# Saules_kolektoriaus_valdiklis_v1_23.net
KiCad netlist of a schematic drawn in EAGLE
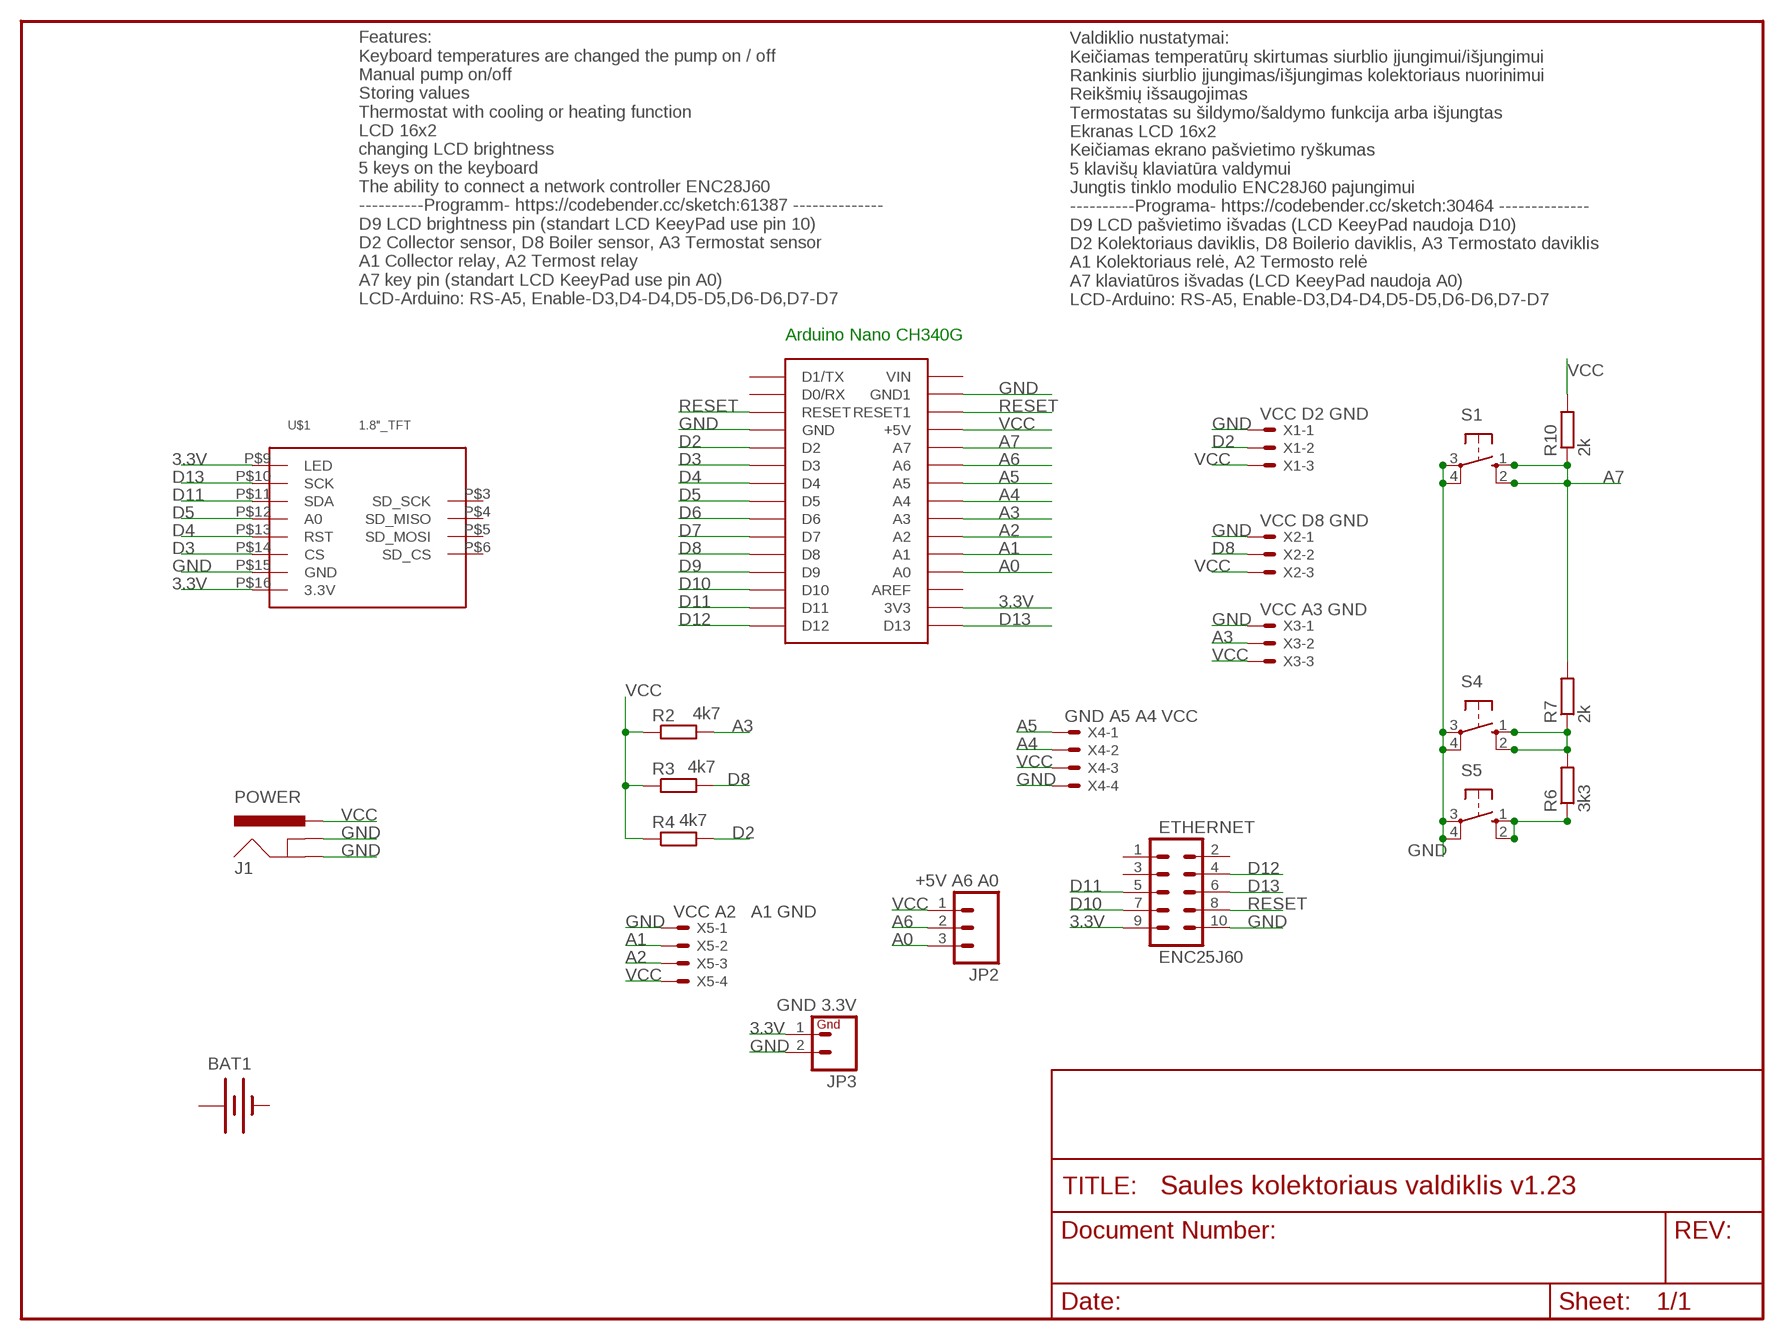
[diagram p0: schematic, sheet 1]

(export (version "E")
  (design (tool "Eeschema 10.0.6"))
  (components
    (comp (ref "ARDUINONANOCH340G")
      (value "ARDUINONANO")
      (footprint "eagle-import:PDIP-32")
      (libsource (lib "eagle-import") (part "ARDUINONANO"))
    )
    (comp (ref "BAT1")
      (value "BATTERY20PTH")
      (footprint "eagle-import:BATTCOM_20MM_PTH")
      (libsource (lib "eagle-import") (part "BATTERY20PTH"))
    )
    (comp (ref "ETHERNET")
      (value "ENC25J60")
      (footprint "eagle-import:AVR_ICSP")
      (libsource (lib "eagle-import") (part "M05X2PTH"))
    )
    (comp (ref "J1")
      (value "POWER")
      (footprint "eagle-import:POWER_JACK_PTH_LOCK")
      (libsource (lib "eagle-import") (part "POWER_JACKPTH_LOCK"))
    )
    (comp (ref "JP2")
      (value "+5V A6 A0")
      (footprint "eagle-import:1X03")
      (libsource (lib "eagle-import") (part "M03PTH"))
    )
    (comp (ref "JP3")
      (value "GND 3.3V")
      (footprint "eagle-import:1X02")
      (libsource (lib "eagle-import") (part "M02PTH"))
    )
    (comp (ref "R2")
      (value "4k7")
      (footprint "eagle-import:0207_10")
      (libsource (lib "eagle-import") (part "R-EU_0207/10"))
    )
    (comp (ref "R3")
      (value "4k7")
      (footprint "eagle-import:0207_10")
      (libsource (lib "eagle-import") (part "R-EU_0207/10"))
    )
    (comp (ref "R4")
      (value "4k7")
      (footprint "eagle-import:0207_10")
      (libsource (lib "eagle-import") (part "R-EU_0207/10"))
    )
    (comp (ref "R6")
      (value "3k3")
      (footprint "eagle-import:0207_10")
      (libsource (lib "eagle-import") (part "R-EU_0207/10"))
    )
    (comp (ref "R7")
      (value "2k")
      (footprint "eagle-import:0207_10")
      (libsource (lib "eagle-import") (part "R-EU_0207/10"))
    )
    (comp (ref "R10")
      (value "2k")
      (footprint "eagle-import:0207_10")
      (libsource (lib "eagle-import") (part "R-EU_0207/10"))
    )
    (comp (ref "S1")
      (value "10-XX")
      (footprint "eagle-import:B3F-10XX")
      (fields (field (name "MPN") "B3F-1000"))
      (libsource (lib "eagle-import") (part "10-XX"))
    )
    (comp (ref "S4")
      (value "10-XX")
      (footprint "eagle-import:B3F-10XX")
      (fields (field (name "MPN") "B3F-1000"))
      (libsource (lib "eagle-import") (part "10-XX"))
    )
    (comp (ref "S5")
      (value "10-XX")
      (footprint "eagle-import:B3F-10XX")
      (fields (field (name "MPN") "B3F-1000"))
      (libsource (lib "eagle-import") (part "10-XX"))
    )
    (comp (ref "U$1")
      (value "1.8\"_TFT")
      (footprint "eagle-import:1.8__TFT")
      (libsource (lib "eagle-import") (part "1.8{dblquote}_TFT"))
    )
    (comp (ref "X1")
      (value "VCC D2 GND")
      (footprint "eagle-import:22-23-2031")
      (fields (field (name "MF") "MOLEX") (field (name "MPN") "22-23-2031"))
      (libsource (lib "eagle-import") (part "22-23-2031"))
    )
    (comp (ref "X2")
      (value "VCC D8 GND")
      (footprint "eagle-import:22-23-2031")
      (fields (field (name "MF") "MOLEX") (field (name "MPN") "22-23-2031"))
      (libsource (lib "eagle-import") (part "22-23-2031"))
    )
    (comp (ref "X3")
      (value "VCC A3 GND")
      (footprint "eagle-import:22-23-2031")
      (fields (field (name "MF") "MOLEX") (field (name "MPN") "22-23-2031"))
      (libsource (lib "eagle-import") (part "22-23-2031"))
    )
    (comp (ref "X4")
      (value "GND A5 A4 VCC")
      (footprint "eagle-import:22-23-2041")
      (fields (field (name "MF") "MOLEX") (field (name "MPN") "22-23-2041"))
      (libsource (lib "eagle-import") (part "22-23-2041"))
    )
    (comp (ref "X5")
      (value "VCC A2 A1 GND")
      (footprint "eagle-import:22-23-2041")
      (fields (field (name "MF") "MOLEX") (field (name "MPN") "22-23-2041"))
      (libsource (lib "eagle-import") (part "22-23-2041"))
    )
  )
  (nets
    (net (code "1") (name "/+") (class "Default")
      (node (ref "BAT1") (pin "1") (pinfunction "+_1") (pintype "power_in"))
    )
    (net (code "2") (name "/-") (class "Default")
      (node (ref "BAT1") (pin "2") (pinfunction "-_2") (pintype "power_in"))
    )
    (net (code "3") (name "/3.3V") (class "Default")
      (node (ref "ARDUINONANOCH340G") (pin "3V3") (pinfunction "3V3_3V3") (pintype "bidirectional"))
      (node (ref "ETHERNET") (pin "9") (pinfunction "9_9") (pintype "passive"))
      (node (ref "JP3") (pin "1") (pinfunction "1_1") (pintype "passive"))
      (node (ref "U$1") (pin "P$16") (pinfunction "3.3V_P$16") (pintype "bidirectional"))
      (node (ref "U$1") (pin "P$9") (pinfunction "LED_P$9") (pintype "bidirectional"))
    )
    (net (code "4") (name "/A0") (class "Default")
      (node (ref "ARDUINONANOCH340G") (pin "A0") (pinfunction "A0_A0") (pintype "bidirectional"))
      (node (ref "JP2") (pin "3") (pinfunction "3_3") (pintype "passive"))
    )
    (net (code "5") (name "/A1") (class "Default")
      (node (ref "ARDUINONANOCH340G") (pin "A1") (pinfunction "A1_A1") (pintype "bidirectional"))
      (node (ref "X5") (pin "2") (pinfunction "S_2") (pintype "passive"))
    )
    (net (code "6") (name "/A2") (class "Default")
      (node (ref "ARDUINONANOCH340G") (pin "A2") (pinfunction "A2_A2") (pintype "bidirectional"))
      (node (ref "X5") (pin "3") (pinfunction "S_3") (pintype "passive"))
    )
    (net (code "7") (name "/A3") (class "Default")
      (node (ref "ARDUINONANOCH340G") (pin "A3") (pinfunction "A3_A3") (pintype "bidirectional"))
      (node (ref "R2") (pin "2") (pinfunction "2_2") (pintype "passive"))
      (node (ref "X3") (pin "2") (pinfunction "S_2") (pintype "passive"))
    )
    (net (code "8") (name "/A4") (class "Default")
      (node (ref "ARDUINONANOCH340G") (pin "A4") (pinfunction "A4_A4") (pintype "bidirectional"))
      (node (ref "X4") (pin "2") (pinfunction "S_2") (pintype "passive"))
    )
    (net (code "9") (name "/A5") (class "Default")
      (node (ref "ARDUINONANOCH340G") (pin "A5") (pinfunction "A5_A5") (pintype "bidirectional"))
      (node (ref "X4") (pin "1") (pinfunction "S_1") (pintype "passive"))
    )
    (net (code "10") (name "/A6") (class "Default")
      (node (ref "ARDUINONANOCH340G") (pin "A6") (pinfunction "A6_A6") (pintype "bidirectional"))
      (node (ref "JP2") (pin "2") (pinfunction "2_2") (pintype "passive"))
    )
    (net (code "11") (name "/A7") (class "Default")
      (node (ref "ARDUINONANOCH340G") (pin "A7") (pinfunction "A7_A7") (pintype "bidirectional"))
      (node (ref "R10") (pin "1") (pinfunction "1_1") (pintype "passive"))
      (node (ref "R7") (pin "2") (pinfunction "2_2") (pintype "passive"))
      (node (ref "S1") (pin "1") (pinfunction "S_1") (pintype "passive"))
      (node (ref "S1") (pin "2") (pinfunction "S1_2") (pintype "passive"))
    )
    (net (code "12") (name "/D2") (class "Default")
      (node (ref "ARDUINONANOCH340G") (pin "D2") (pinfunction "D2_D2") (pintype "bidirectional"))
      (node (ref "R4") (pin "2") (pinfunction "2_2") (pintype "passive"))
      (node (ref "X1") (pin "2") (pinfunction "S_2") (pintype "passive"))
    )
    (net (code "13") (name "/D3") (class "Default")
      (node (ref "ARDUINONANOCH340G") (pin "D3") (pinfunction "D3_D3") (pintype "bidirectional"))
      (node (ref "U$1") (pin "P$14") (pinfunction "CS_P$14") (pintype "bidirectional"))
    )
    (net (code "14") (name "/D4") (class "Default")
      (node (ref "ARDUINONANOCH340G") (pin "D4") (pinfunction "D4_D4") (pintype "bidirectional"))
      (node (ref "U$1") (pin "P$13") (pinfunction "RST_P$13") (pintype "bidirectional"))
    )
    (net (code "15") (name "/D5") (class "Default")
      (node (ref "ARDUINONANOCH340G") (pin "D5") (pinfunction "D5_D5") (pintype "bidirectional"))
      (node (ref "U$1") (pin "P$12") (pinfunction "A0_P$12") (pintype "bidirectional"))
    )
    (net (code "16") (name "/D6") (class "Default")
      (node (ref "ARDUINONANOCH340G") (pin "D6") (pinfunction "D6_D6") (pintype "bidirectional"))
    )
    (net (code "17") (name "/D7") (class "Default")
      (node (ref "ARDUINONANOCH340G") (pin "D7") (pinfunction "D7_D7") (pintype "bidirectional"))
    )
    (net (code "18") (name "/D8") (class "Default")
      (node (ref "ARDUINONANOCH340G") (pin "D8") (pinfunction "D8_D8") (pintype "bidirectional"))
      (node (ref "R3") (pin "2") (pinfunction "2_2") (pintype "passive"))
      (node (ref "X2") (pin "2") (pinfunction "S_2") (pintype "passive"))
    )
    (net (code "19") (name "/D9") (class "Default")
      (node (ref "ARDUINONANOCH340G") (pin "D9") (pinfunction "D9_D9") (pintype "bidirectional"))
    )
    (net (code "20") (name "/D10") (class "Default")
      (node (ref "ARDUINONANOCH340G") (pin "D10") (pinfunction "D10_D10") (pintype "bidirectional"))
      (node (ref "ETHERNET") (pin "7") (pinfunction "7_7") (pintype "passive"))
    )
    (net (code "21") (name "/D11") (class "Default")
      (node (ref "ARDUINONANOCH340G") (pin "D11") (pinfunction "D11_D11") (pintype "bidirectional"))
      (node (ref "ETHERNET") (pin "5") (pinfunction "5_5") (pintype "passive"))
      (node (ref "U$1") (pin "P$11") (pinfunction "SDA_P$11") (pintype "bidirectional"))
    )
    (net (code "22") (name "/D12") (class "Default")
      (node (ref "ARDUINONANOCH340G") (pin "D12") (pinfunction "D12_D12") (pintype "bidirectional"))
      (node (ref "ETHERNET") (pin "4") (pinfunction "4_4") (pintype "passive"))
    )
    (net (code "23") (name "/D13") (class "Default")
      (node (ref "ARDUINONANOCH340G") (pin "D13") (pinfunction "D13_D13") (pintype "bidirectional"))
      (node (ref "ETHERNET") (pin "6") (pinfunction "6_6") (pintype "passive"))
      (node (ref "U$1") (pin "P$10") (pinfunction "SCK_P$10") (pintype "bidirectional"))
    )
    (net (code "24") (name "/GND") (class "Default")
      (node (ref "ARDUINONANOCH340G") (pin "GND") (pinfunction "GND_GND") (pintype "bidirectional"))
      (node (ref "ARDUINONANOCH340G") (pin "GND1") (pinfunction "GND1_GND1") (pintype "bidirectional"))
      (node (ref "ETHERNET") (pin "10") (pinfunction "10_10") (pintype "passive"))
      (node (ref "J1") (pin "GND") (pinfunction "GND_GND") (pintype "bidirectional"))
      (node (ref "J1") (pin "GNDBREAK") (pinfunction "GNDBREAK_GNDBREAK") (pintype "bidirectional"))
      (node (ref "JP3") (pin "2") (pinfunction "2_2") (pintype "passive"))
      (node (ref "S1") (pin "3") (pinfunction "P_3") (pintype "passive"))
      (node (ref "S1") (pin "4") (pinfunction "P1_4") (pintype "passive"))
      (node (ref "S4") (pin "3") (pinfunction "P_3") (pintype "passive"))
      (node (ref "S4") (pin "4") (pinfunction "P1_4") (pintype "passive"))
      (node (ref "S5") (pin "3") (pinfunction "P_3") (pintype "passive"))
      (node (ref "S5") (pin "4") (pinfunction "P1_4") (pintype "passive"))
      (node (ref "U$1") (pin "P$15") (pinfunction "GND_P$15") (pintype "bidirectional"))
      (node (ref "X1") (pin "1") (pinfunction "S_1") (pintype "passive"))
      (node (ref "X2") (pin "1") (pinfunction "S_1") (pintype "passive"))
      (node (ref "X3") (pin "1") (pinfunction "S_1") (pintype "passive"))
      (node (ref "X4") (pin "4") (pinfunction "S_4") (pintype "passive"))
      (node (ref "X5") (pin "1") (pinfunction "S_1") (pintype "passive"))
    )
    (net (code "25") (name "/RESET") (class "Default")
      (node (ref "ARDUINONANOCH340G") (pin "RESET") (pinfunction "RESET_RESET") (pintype "bidirectional"))
      (node (ref "ARDUINONANOCH340G") (pin "RESET1") (pinfunction "RESET1_RESET1") (pintype "bidirectional"))
      (node (ref "ETHERNET") (pin "8") (pinfunction "8_8") (pintype "passive"))
    )
    (net (code "26") (name "/VCC") (class "Default")
      (node (ref "ARDUINONANOCH340G") (pin "+5V") (pinfunction "+5V_+5V") (pintype "bidirectional"))
      (node (ref "J1") (pin "PWR") (pinfunction "PWR_PWR") (pintype "bidirectional"))
      (node (ref "JP2") (pin "1") (pinfunction "1_1") (pintype "passive"))
      (node (ref "R10") (pin "2") (pinfunction "2_2") (pintype "passive"))
      (node (ref "R2") (pin "1") (pinfunction "1_1") (pintype "passive"))
      (node (ref "R3") (pin "1") (pinfunction "1_1") (pintype "passive"))
      (node (ref "R4") (pin "1") (pinfunction "1_1") (pintype "passive"))
      (node (ref "X1") (pin "3") (pinfunction "S_3") (pintype "passive"))
      (node (ref "X2") (pin "3") (pinfunction "S_3") (pintype "passive"))
      (node (ref "X3") (pin "3") (pinfunction "S_3") (pintype "passive"))
      (node (ref "X4") (pin "3") (pinfunction "S_3") (pintype "passive"))
      (node (ref "X5") (pin "4") (pinfunction "S_4") (pintype "passive"))
    )
    (net (code "27") (name "Net-(S4-S)") (class "Default")
      (node (ref "R6") (pin "2") (pinfunction "2_2") (pintype "passive"))
      (node (ref "R7") (pin "1") (pinfunction "1_1") (pintype "passive"))
      (node (ref "S4") (pin "1") (pinfunction "S_1") (pintype "passive"))
      (node (ref "S4") (pin "2") (pinfunction "S1_2") (pintype "passive"))
    )
    (net (code "28") (name "Net-(S5-S)") (class "Default")
      (node (ref "R6") (pin "1") (pinfunction "1_1") (pintype "passive"))
      (node (ref "S5") (pin "1") (pinfunction "S_1") (pintype "passive"))
      (node (ref "S5") (pin "2") (pinfunction "S1_2") (pintype "passive"))
    )
    (net (code "29") (name "unconnected-(ARDUINONANOCH340G-PadAREF)") (class "Default")
      (node (ref "ARDUINONANOCH340G") (pin "AREF") (pinfunction "AREF_AREF") (pintype "bidirectional"))
    )
    (net (code "30") (name "unconnected-(ARDUINONANOCH340G-PadD0{slash}RX)") (class "Default")
      (node (ref "ARDUINONANOCH340G") (pin "D0/RX") (pinfunction "D0/RX_D0/RX") (pintype "bidirectional"))
    )
    (net (code "31") (name "unconnected-(ARDUINONANOCH340G-PadD1{slash}TX)") (class "Default")
      (node (ref "ARDUINONANOCH340G") (pin "D1/TX") (pinfunction "D1/TX_D1/TX") (pintype "bidirectional"))
    )
    (net (code "32") (name "unconnected-(ARDUINONANOCH340G-PadVIN)") (class "Default")
      (node (ref "ARDUINONANOCH340G") (pin "VIN") (pinfunction "VIN_VIN") (pintype "bidirectional"))
    )
    (net (code "33") (name "unconnected-(ETHERNET-Pad1)") (class "Default")
      (node (ref "ETHERNET") (pin "1") (pinfunction "1_1") (pintype "passive"))
    )
    (net (code "34") (name "unconnected-(ETHERNET-Pad2)") (class "Default")
      (node (ref "ETHERNET") (pin "2") (pinfunction "2_2") (pintype "passive"))
    )
    (net (code "35") (name "unconnected-(ETHERNET-Pad3)") (class "Default")
      (node (ref "ETHERNET") (pin "3") (pinfunction "3_3") (pintype "passive"))
    )
    (net (code "36") (name "unconnected-(U$1-SD_CS-PadP$6)") (class "Default")
      (node (ref "U$1") (pin "P$6") (pinfunction "SD_CS_P$6") (pintype "bidirectional"))
    )
    (net (code "37") (name "unconnected-(U$1-SD_MISO-PadP$4)") (class "Default")
      (node (ref "U$1") (pin "P$4") (pinfunction "SD_MISO_P$4") (pintype "bidirectional"))
    )
    (net (code "38") (name "unconnected-(U$1-SD_MOSI-PadP$5)") (class "Default")
      (node (ref "U$1") (pin "P$5") (pinfunction "SD_MOSI_P$5") (pintype "bidirectional"))
    )
    (net (code "39") (name "unconnected-(U$1-SD_SCK-PadP$3)") (class "Default")
      (node (ref "U$1") (pin "P$3") (pinfunction "SD_SCK_P$3") (pintype "bidirectional"))
    )
  )
)
